# Sheet2.net
KiCad netlist of a schematic drawn in Altium Designer
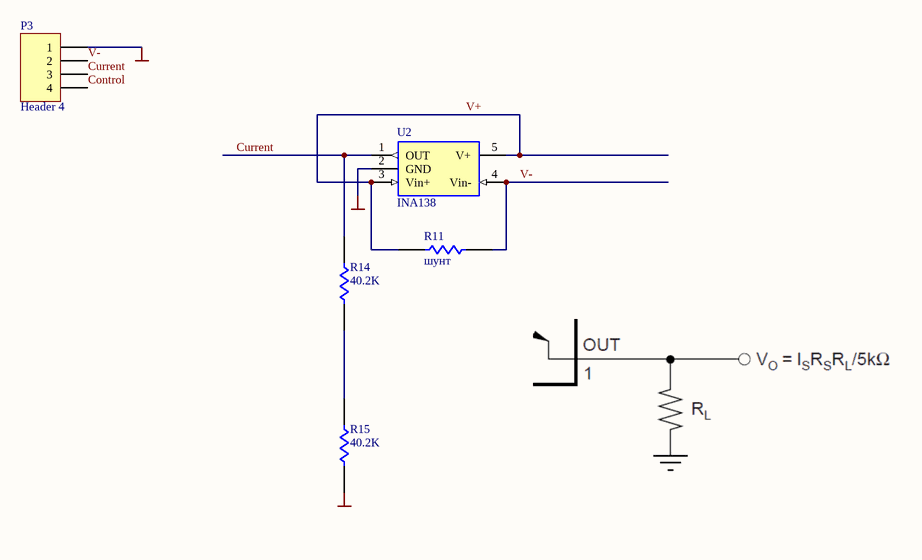
[diagram p0: Sheet2.SchDoc]

(export (version "E")
  (design (tool "Eeschema 10.0.6"))
  (components
    (comp (ref "P3")
      (value "Header 4")
      (footprint "HDR1X4")
      (description "Header, 4-Pin")
      (fields (field (name "PUBLISHER") "Altium Limited"))
      (libsource (lib "Miscellaneous Connectors") (part "Header 4"))
    )
    (comp (ref "R11")
      (value "шунт")
      (footprint "6-0805_M")
      (fields (field (name "PUBLISHER") "Altium Limited"))
      (libsource (lib "Project") (part "Resistor"))
    )
    (comp (ref "R14")
      (value "40.2K")
      (footprint "6-0805_M")
      (fields (field (name "PUBLISHER") "Altium Limited"))
      (libsource (lib "Project") (part "Resistor"))
    )
    (comp (ref "R15")
      (value "40.2K")
      (footprint "6-0805_M")
      (fields (field (name "PUBLISHER") "Altium Limited"))
      (libsource (lib "Project") (part "Resistor"))
    )
    (comp (ref "U2")
      (value "INA138")
      (footprint "SOT23-5_M")
      (description "INA 138 Current monitor")
      (fields (field (name "PUBLISHER") "Altium Limited"))
      (libsource (lib "Project") (part "INA138"))
    )
  )
  (nets
    (net (code "1") (name "/Control") (class "Default")
      (node (ref "P3") (pin "4") (pinfunction "4_4") (pintype "passive"))
    )
    (net (code "2") (name "/Current") (class "Default")
      (node (ref "P3") (pin "3") (pinfunction "3_3") (pintype "passive"))
      (node (ref "R14") (pin "1") (pinfunction "1_1") (pintype "passive"))
      (node (ref "U2") (pin "1") (pinfunction "OUT_1") (pintype "output"))
    )
    (net (code "3") (name "/V+") (class "Default")
      (node (ref "R11") (pin "1") (pinfunction "1_1") (pintype "passive"))
      (node (ref "U2") (pin "3") (pinfunction "Vin+_3") (pintype "input"))
      (node (ref "U2") (pin "5") (pinfunction "V+_5") (pintype "power_in"))
    )
    (net (code "4") (name "/V-") (class "Default")
      (node (ref "P3") (pin "2") (pinfunction "2_2") (pintype "passive"))
      (node (ref "R11") (pin "2") (pinfunction "2_2") (pintype "passive"))
      (node (ref "U2") (pin "4") (pinfunction "Vin-_4") (pintype "input"))
    )
    (net (code "5") (name "GND") (class "Default")
      (node (ref "P3") (pin "1") (pinfunction "1_1") (pintype "passive"))
      (node (ref "R15") (pin "2") (pinfunction "2_2") (pintype "passive"))
      (node (ref "U2") (pin "2") (pinfunction "GND_2") (pintype "power_in"))
    )
    (net (code "6") (name "Net-(R14-Pad2)") (class "Default")
      (node (ref "R14") (pin "2") (pinfunction "2_2") (pintype "passive"))
      (node (ref "R15") (pin "1") (pinfunction "1_1") (pintype "passive"))
    )
  )
)
